# ADS_AFE.net
KiCad netlist of a schematic drawn in Altium Designer
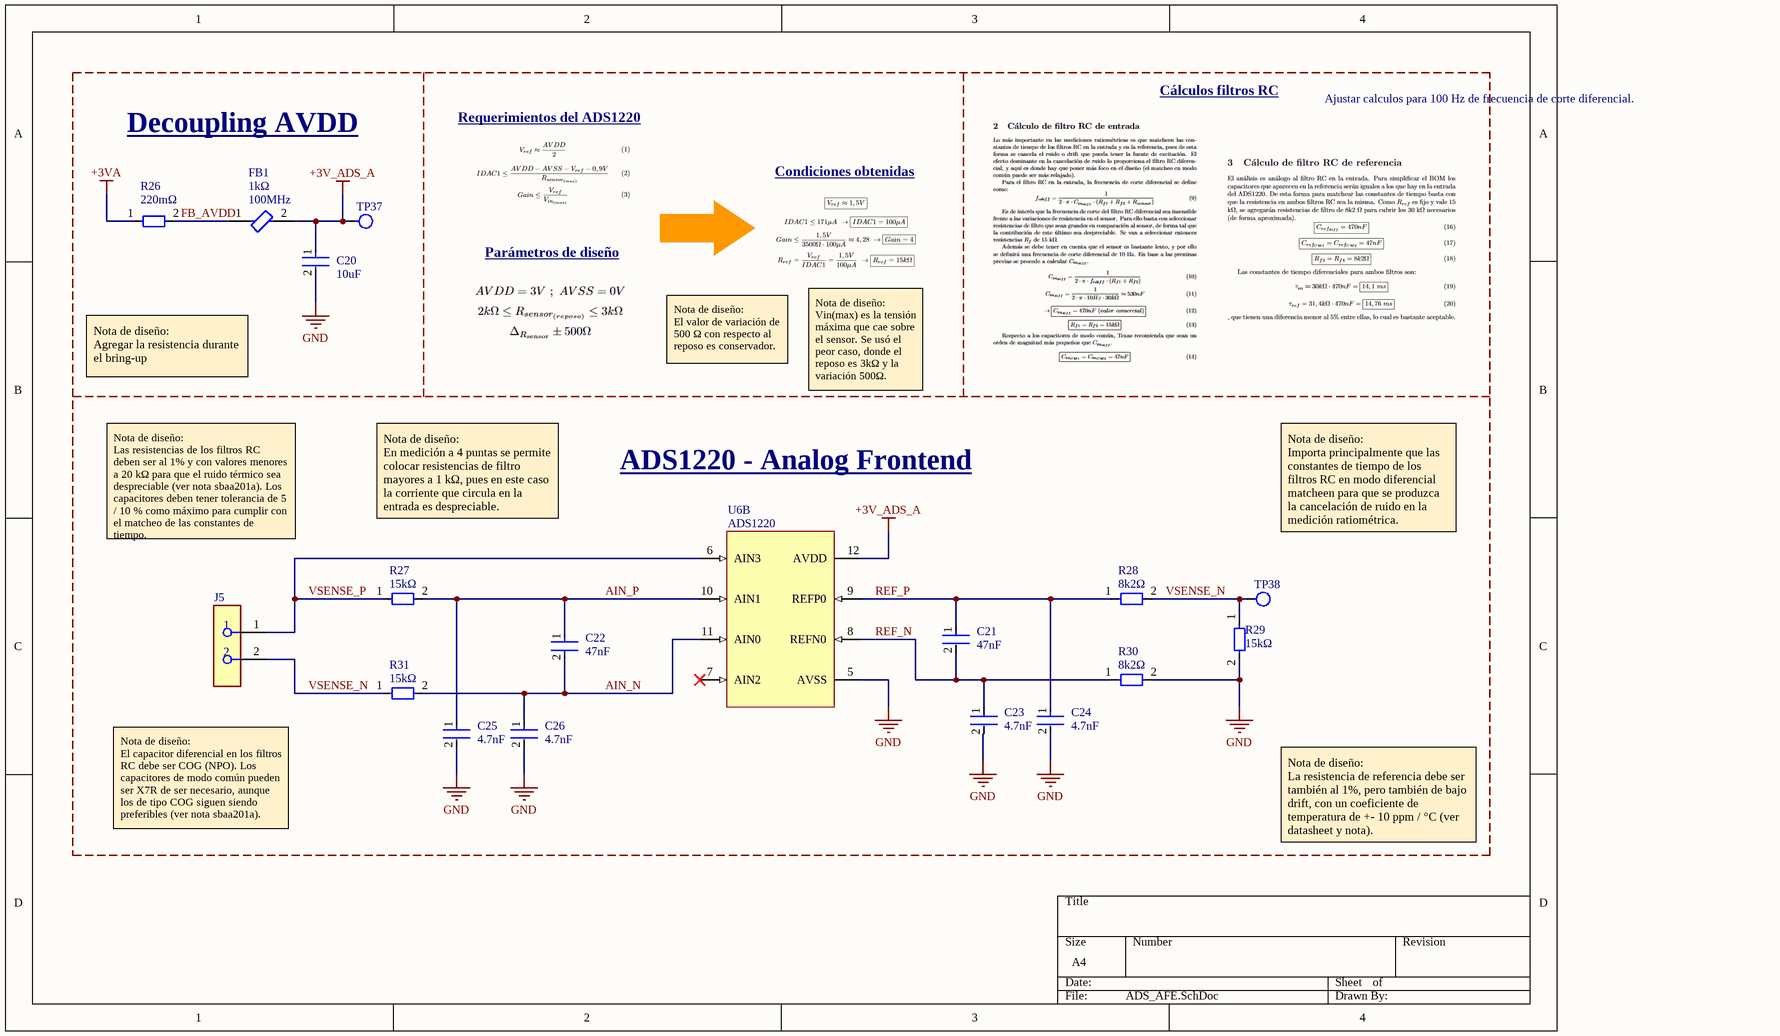
[diagram p0: ADS_AFE.SchDoc]

(export (version "E")
  (design (tool "Eeschema 10.0.6"))
  (components
    (comp (ref "C20")
      (value "10uF")
      (footprint "CAP_0603")
      (description "Cap 10 uF 10V X7R 0603")
      (fields (field (name "CAPACITANCE") "10uF") (field (name "TOLERANCE") "10%"))
      (libsource (lib "Passive_Components") (part "Generic C"))
    )
    (comp (ref "C21")
      (value "470nF")
      (footprint "CAP_0603")
      (description "Cap 470 nF 10V C0G 0603")
      (fields (field (name "CAPACITANCE") "47nF") (field (name "TOLERANCE") "10%"))
      (libsource (lib "Passive_Components") (part "Generic C"))
    )
    (comp (ref "C22")
      (value "470nF")
      (footprint "CAP_0603")
      (description "Cap 470 nF 10V C0G 0603")
      (fields (field (name "CAPACITANCE") "47nF") (field (name "TOLERANCE") "10%"))
      (libsource (lib "Passive_Components") (part "Generic C"))
    )
    (comp (ref "C23")
      (value "47nF")
      (footprint "CAP_0603")
      (description "Cap 47 nF 10V X7R 0603")
      (fields (field (name "CAPACITANCE") "4.7nF") (field (name "TOLERANCE") "10%"))
      (libsource (lib "Passive_Components") (part "Generic C"))
    )
    (comp (ref "C24")
      (value "47nF")
      (footprint "CAP_0603")
      (description "Cap 47 nF 10V X7R 0603")
      (fields (field (name "CAPACITANCE") "4.7nF") (field (name "TOLERANCE") "10%"))
      (libsource (lib "Passive_Components") (part "Generic C"))
    )
    (comp (ref "C25")
      (value "47nF")
      (footprint "CAP_0603")
      (description "Cap 47 nF 10V X7R 0603")
      (fields (field (name "CAPACITANCE") "4.7nF") (field (name "TOLERANCE") "10%"))
      (libsource (lib "Passive_Components") (part "Generic C"))
    )
    (comp (ref "C26")
      (value "47nF")
      (footprint "CAP_0603")
      (description "Cap 47 nF 10V X7R 0603")
      (fields (field (name "CAPACITANCE") "4.7nF") (field (name "TOLERANCE") "10%"))
      (libsource (lib "Passive_Components") (part "Generic C"))
    )
    (comp (ref "FB1")
      (value "MPZ2012S102AT000")
      (footprint "FP-MPZ2012-IPC_B")
      (description "FERRITE BEAD 1 KOHM 0805 1LN")
      (fields
        (field (name "IMPEDANCE") "1kΩ")
        (field (name "TEST FREQUENCY") "100MHz")
        (field (name "TOLERANCE") "25%")
      )
      (libsource (lib "Altium Content Vault") (part "5f30dd21d616792df468990f7003faa"))
    )
    (comp (ref "J5")
      (value "PPTC021LGBN-RC")
      (footprint "FP-PPTC021LGBN-RC-MFG")
      (description "PPTC021LGBN-RC 2 Position Total Single Row 2.54 mm Pitch Right Angle Female Header")
      (libsource (lib "Altium Content Vault") (part "78f693cf7826bc156400b272d5a8ffe"))
    )
    (comp (ref "R26")
      (value "220mΩ")
      (footprint "RES_0603")
      (description "RES  220mOhm 1% 0603")
      (fields (field (name "Comment") "220mOhm"))
      (libsource (lib "Passive_Components") (part "Generic R"))
    )
    (comp (ref "R27")
      (value "15kΩ")
      (footprint "RES_0603")
      (description "RES  15k 1% 0603")
      (fields (field (name "Comment") "15k"))
      (libsource (lib "Passive_Components") (part "Generic R"))
    )
    (comp (ref "R28")
      (value "8k2Ω")
      (footprint "RES_0603")
      (description "RES  8k2 1% 0603")
      (fields (field (name "Comment") "8k2"))
      (libsource (lib "Passive_Components") (part "Generic R"))
    )
    (comp (ref "R29")
      (value "15kΩ")
      (footprint "RES_0603")
      (description "RES  8k2 1% 0603, low drift  +- 10 ppm / °C.")
      (fields (field (name "Comment") "15k REF"))
      (libsource (lib "") (part "Generic R_1"))
    )
    (comp (ref "R30")
      (value "8k2Ω")
      (footprint "RES_0603")
      (description "RES  8k2 1% 0603")
      (fields (field (name "Comment") "8k2"))
      (libsource (lib "Passive_Components") (part "Generic R"))
    )
    (comp (ref "R31")
      (value "15kΩ")
      (footprint "RES_0603")
      (description "RES  15k 1% 0603")
      (fields (field (name "Comment") "15k"))
      (libsource (lib "Passive_Components") (part "Generic R"))
    )
    (comp (ref "TP37")
      (value "Testpoint SMD")
      (footprint "Testpoint_SMD")
      (description "Testpoint SMD de 1mm de diametro.")
      (libsource (lib "Connectors") (part "Testpoint_SMD"))
    )
    (comp (ref "TP38")
      (value "Testpoint SMD")
      (footprint "Testpoint_SMD")
      (description "Testpoint SMD de 1mm de diametro.")
      (libsource (lib "Connectors") (part "Testpoint_SMD"))
    )
    (comp (ref "U6")
      (value "ADS1220")
      (footprint "TSSOP-16")
      (description "ADS1220 4-Channel, 2-kSPS, Low-Power, 24-Bit ADC with Integrated PGA and Reference")
      (libsource (lib "ADC_DAC") (part "ADS1220"))
    )
  )
  (nets
    (net (code "1") (name "+3VA") (class "Default")
      (node (ref "R26") (pin "1") (pinfunction "1_1") (pintype "passive"))
    )
    (net (code "2") (name "+3V_ADS_A") (class "Default")
      (node (ref "C20") (pin "1") (pinfunction "1_1") (pintype "passive"))
      (node (ref "FB1") (pin "2") (pinfunction "2_2") (pintype "passive"))
      (node (ref "TP37") (pin "1") (pinfunction "1_1") (pintype "passive"))
      (node (ref "U6") (pin "12") (pinfunction "AVDD_12") (pintype "power_in"))
    )
    (net (code "3") (name "/AIN_N") (class "Default")
      (node (ref "C22") (pin "2") (pinfunction "2_2") (pintype "passive"))
      (node (ref "C26") (pin "1") (pinfunction "1_1") (pintype "passive"))
      (node (ref "R31") (pin "2") (pinfunction "2_2") (pintype "passive"))
      (node (ref "U6") (pin "11") (pinfunction "AIN0_11") (pintype "input"))
    )
    (net (code "4") (name "/AIN_P") (class "Default")
      (node (ref "C22") (pin "1") (pinfunction "1_1") (pintype "passive"))
      (node (ref "C25") (pin "1") (pinfunction "1_1") (pintype "passive"))
      (node (ref "R27") (pin "2") (pinfunction "2_2") (pintype "passive"))
      (node (ref "U6") (pin "10") (pinfunction "AIN1_10") (pintype "input"))
    )
    (net (code "5") (name "/FB_AVDD") (class "Default")
      (node (ref "FB1") (pin "1") (pinfunction "1_1") (pintype "passive"))
      (node (ref "R26") (pin "2") (pinfunction "2_2") (pintype "passive"))
    )
    (net (code "6") (name "/REF_N") (class "Default")
      (node (ref "C21") (pin "2") (pinfunction "2_2") (pintype "passive"))
      (node (ref "C23") (pin "1") (pinfunction "1_1") (pintype "passive"))
      (node (ref "R30") (pin "1") (pinfunction "1_1") (pintype "passive"))
      (node (ref "U6") (pin "8") (pinfunction "REFN0_8") (pintype "input"))
    )
    (net (code "7") (name "/REF_P") (class "Default")
      (node (ref "C21") (pin "1") (pinfunction "1_1") (pintype "passive"))
      (node (ref "C24") (pin "1") (pinfunction "1_1") (pintype "passive"))
      (node (ref "R28") (pin "1") (pinfunction "1_1") (pintype "passive"))
      (node (ref "U6") (pin "9") (pinfunction "REFP0_9") (pintype "input"))
    )
    (net (code "8") (name "/VSENSE_N") (class "Default")
      (node (ref "J5") (pin "2") (pinfunction "2_2") (pintype "passive"))
      (node (ref "R28") (pin "2") (pinfunction "2_2") (pintype "passive"))
      (node (ref "R29") (pin "1") (pinfunction "1_1") (pintype "passive"))
      (node (ref "R31") (pin "1") (pinfunction "1_1") (pintype "passive"))
      (node (ref "TP38") (pin "1") (pinfunction "1_1") (pintype "passive"))
    )
    (net (code "9") (name "/VSENSE_P") (class "Default")
      (node (ref "J5") (pin "1") (pinfunction "1_1") (pintype "passive"))
      (node (ref "R27") (pin "1") (pinfunction "1_1") (pintype "passive"))
      (node (ref "U6") (pin "6") (pinfunction "AIN3_6") (pintype "input"))
    )
    (net (code "10") (name "GND") (class "Default")
      (node (ref "C20") (pin "2") (pinfunction "2_2") (pintype "passive"))
      (node (ref "C23") (pin "2") (pinfunction "2_2") (pintype "passive"))
      (node (ref "C24") (pin "2") (pinfunction "2_2") (pintype "passive"))
      (node (ref "C25") (pin "2") (pinfunction "2_2") (pintype "passive"))
      (node (ref "C26") (pin "2") (pinfunction "2_2") (pintype "passive"))
      (node (ref "R29") (pin "2") (pinfunction "2_2") (pintype "passive"))
      (node (ref "R30") (pin "2") (pinfunction "2_2") (pintype "passive"))
      (node (ref "U6") (pin "5") (pinfunction "AVSS_5") (pintype "power_in"))
    )
    (net (code "11") (name "unconnected-(U6B-AIN2-Pad7)") (class "Default")
      (node (ref "U6") (pin "7") (pinfunction "AIN2_7") (pintype "input+no_connect"))
    )
  )
)
